# ospi_v143.net
KiCad netlist of a schematic drawn in EAGLE
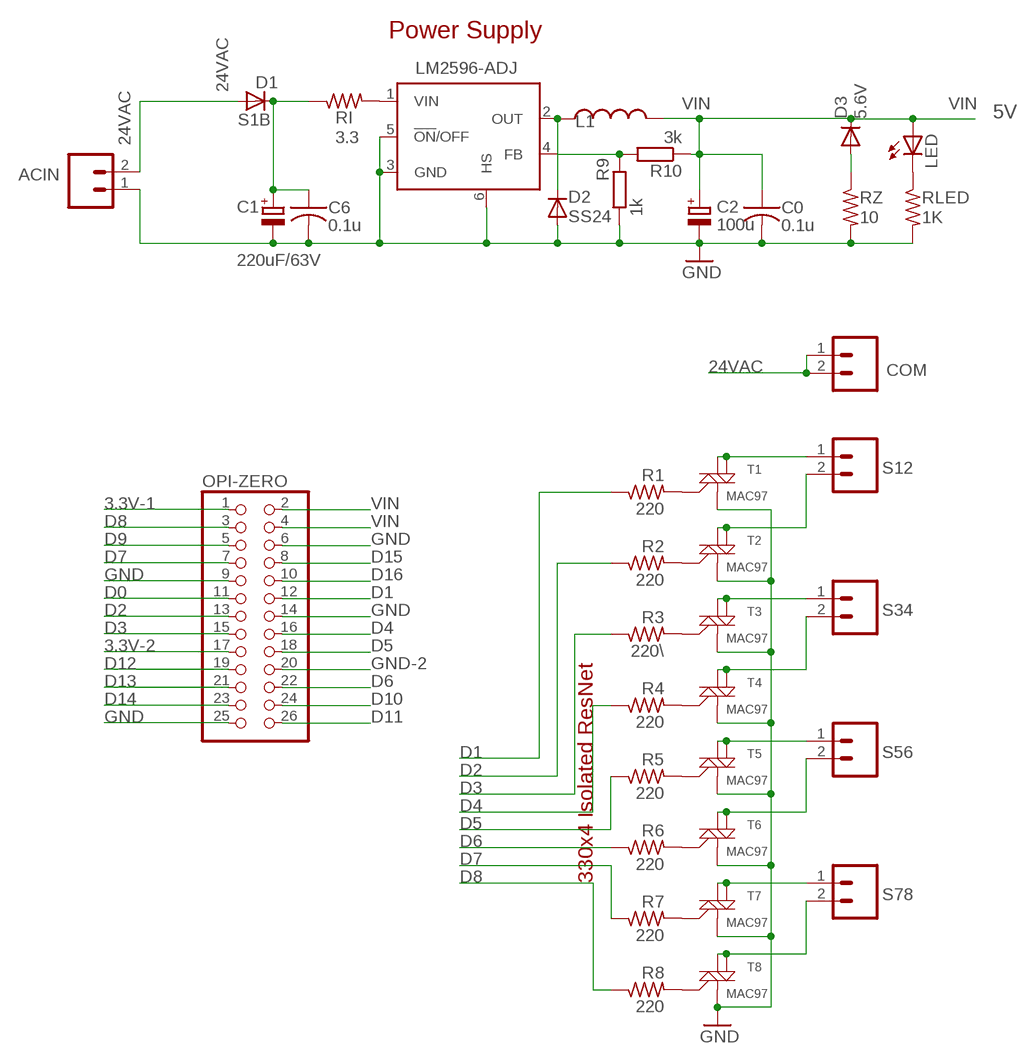
[diagram p0: schematic, sheet 1]

(export (version "E")
  (design (tool "Eeschema 10.0.6"))
  (components
    (comp (ref "ACIN")
      (value "M025MM-X")
      (footprint "eagle-import:SCREWTERMINAL-5MM-2-X")
      (libsource (lib "eagle-import") (part "M025MM-X"))
    )
    (comp (ref "C0")
      (value "0.1u")
      (footprint "eagle-import:C1206")
      (libsource (lib "eagle-import") (part "C-USC1206"))
    )
    (comp (ref "C1")
      (value "220uF/63V")
      (footprint "eagle-import:PANASONIC_E")
      (libsource (lib "eagle-import") (part "CPOL-EUE"))
    )
    (comp (ref "C2")
      (value "100u")
      (footprint "eagle-import:PANASONIC_E")
      (libsource (lib "eagle-import") (part "CPOL-EUE"))
    )
    (comp (ref "C6")
      (value "0.1u")
      (footprint "eagle-import:C1206")
      (libsource (lib "eagle-import") (part "C-USC1206"))
    )
    (comp (ref "COM")
      (value "M025MM-X")
      (footprint "eagle-import:SCREWTERMINAL-5MM-2-X")
      (libsource (lib "eagle-import") (part "M025MM-X"))
    )
    (comp (ref "D1")
      (value "S1B")
      (footprint "eagle-import:DO-214AC")
      (libsource (lib "eagle-import") (part "DIODE-DO-214AC"))
    )
    (comp (ref "D2")
      (value "SS24")
      (footprint "eagle-import:SMB")
      (libsource (lib "eagle-import") (part "DIODE-SMB"))
    )
    (comp (ref "D3")
      (value "5.6V")
      (footprint "eagle-import:MINIMELF")
      (libsource (lib "eagle-import") (part "DIODE-MINIMELF"))
    )
    (comp (ref "L1")
      (value "150uH")
      (footprint "eagle-import:CDRH125")
      (libsource (lib "eagle-import") (part "INDUCTORPWR"))
    )
    (comp (ref "LED")
      (value "LEDCHIPLED_0805")
      (footprint "eagle-import:CHIPLED_0805")
      (libsource (lib "eagle-import") (part "LEDCHIPLED_0805"))
    )
    (comp (ref "LM2596-ADJ")
      (value "LM2596-ADJ")
      (footprint "eagle-import:TO263-5")
      (fields (field (name "MF") "NATIONAL SEMICONDUCTOR") (field (name "MPN") "LM2596S-ADJ/NOPB"))
      (libsource (lib "eagle-import") (part "LM2596S"))
    )
    (comp (ref "OPI-ZERO")
      (value "PINHD-2X13")
      (footprint "eagle-import:2X13")
      (libsource (lib "eagle-import") (part "PINHD-2X13"))
    )
    (comp (ref "R1")
      (value "220")
      (footprint "eagle-import:R0603")
      (libsource (lib "eagle-import") (part "R-US_R0603"))
    )
    (comp (ref "R2")
      (value "220")
      (footprint "eagle-import:R0603")
      (libsource (lib "eagle-import") (part "R-US_R0603"))
    )
    (comp (ref "R3")
      (value "220\\")
      (footprint "eagle-import:R0603")
      (libsource (lib "eagle-import") (part "R-US_R0603"))
    )
    (comp (ref "R4")
      (value "220")
      (footprint "eagle-import:R0603")
      (libsource (lib "eagle-import") (part "R-US_R0603"))
    )
    (comp (ref "R5")
      (value "220")
      (footprint "eagle-import:R0603")
      (libsource (lib "eagle-import") (part "R-US_R0603"))
    )
    (comp (ref "R6")
      (value "220")
      (footprint "eagle-import:R0603")
      (libsource (lib "eagle-import") (part "R-US_R0603"))
    )
    (comp (ref "R7")
      (value "220")
      (footprint "eagle-import:R0603")
      (libsource (lib "eagle-import") (part "R-US_R0603"))
    )
    (comp (ref "R8")
      (value "220")
      (footprint "eagle-import:R0603")
      (libsource (lib "eagle-import") (part "R-US_R0603"))
    )
    (comp (ref "R9")
      (value "1k")
      (footprint "eagle-import:M0805")
      (libsource (lib "eagle-import") (part "R-EU_M0805"))
    )
    (comp (ref "R10")
      (value "3k")
      (footprint "eagle-import:M0805")
      (libsource (lib "eagle-import") (part "R-EU_M0805"))
    )
    (comp (ref "RI")
      (value "3.3")
      (footprint "eagle-import:R2010")
      (libsource (lib "eagle-import") (part "adafruitGood_R-US_R2010"))
    )
    (comp (ref "RLED")
      (value "1K")
      (footprint "eagle-import:R1206")
      (libsource (lib "eagle-import") (part "R-US_R1206"))
    )
    (comp (ref "RZ")
      (value "10")
      (footprint "eagle-import:R2010")
      (libsource (lib "eagle-import") (part "R-US_R2010"))
    )
    (comp (ref "S12")
      (value "M025MM-X")
      (footprint "eagle-import:SCREWTERMINAL-5MM-2-X")
      (libsource (lib "eagle-import") (part "M025MM-X"))
    )
    (comp (ref "S34")
      (value "M025MM-X")
      (footprint "eagle-import:SCREWTERMINAL-5MM-2-X")
      (libsource (lib "eagle-import") (part "M025MM-X"))
    )
    (comp (ref "S56")
      (value "M025MM-X")
      (footprint "eagle-import:SCREWTERMINAL-5MM-2-X")
      (libsource (lib "eagle-import") (part "M025MM-X"))
    )
    (comp (ref "S78")
      (value "M025MM-X")
      (footprint "eagle-import:SCREWTERMINAL-5MM-2-X")
      (libsource (lib "eagle-import") (part "M025MM-X"))
    )
    (comp (ref "T1")
      (value "MAC97")
      (footprint "eagle-import:SOT223")
      (libsource (lib "eagle-import") (part "MAC97SOT223"))
    )
    (comp (ref "T2")
      (value "MAC97")
      (footprint "eagle-import:SOT223")
      (libsource (lib "eagle-import") (part "MAC97SOT223"))
    )
    (comp (ref "T3")
      (value "MAC97")
      (footprint "eagle-import:SOT223")
      (libsource (lib "eagle-import") (part "MAC97SOT223"))
    )
    (comp (ref "T4")
      (value "MAC97")
      (footprint "eagle-import:SOT223")
      (libsource (lib "eagle-import") (part "MAC97SOT223"))
    )
    (comp (ref "T5")
      (value "MAC97")
      (footprint "eagle-import:SOT223")
      (libsource (lib "eagle-import") (part "MAC97SOT223"))
    )
    (comp (ref "T6")
      (value "MAC97")
      (footprint "eagle-import:SOT223")
      (libsource (lib "eagle-import") (part "MAC97SOT223"))
    )
    (comp (ref "T7")
      (value "MAC97")
      (footprint "eagle-import:SOT223")
      (libsource (lib "eagle-import") (part "MAC97SOT223"))
    )
    (comp (ref "T8")
      (value "MAC97")
      (footprint "eagle-import:SOT223")
      (libsource (lib "eagle-import") (part "MAC97SOT223"))
    )
  )
  (nets
    (net (code "1") (name "/3.3V-1") (class "Default")
      (node (ref "OPI-ZERO") (pin "1") (pinfunction "1_1") (pintype "passive"))
    )
    (net (code "2") (name "/3.3V-2") (class "Default")
      (node (ref "OPI-ZERO") (pin "17") (pinfunction "17_17") (pintype "passive"))
    )
    (net (code "3") (name "/24VAC") (class "Default")
      (node (ref "ACIN") (pin "2") (pinfunction "2_2") (pintype "passive"))
      (node (ref "COM") (pin "1") (pinfunction "1_1") (pintype "passive"))
      (node (ref "COM") (pin "2") (pinfunction "2_2") (pintype "passive"))
      (node (ref "D1") (pin "A") (pinfunction "A_A") (pintype "passive"))
    )
    (net (code "4") (name "/D0") (class "Default")
      (node (ref "OPI-ZERO") (pin "11") (pinfunction "11_11") (pintype "passive"))
    )
    (net (code "5") (name "/D1") (class "Default")
      (node (ref "OPI-ZERO") (pin "12") (pinfunction "12_12") (pintype "passive"))
      (node (ref "R1") (pin "1") (pinfunction "1_1") (pintype "passive"))
    )
    (net (code "6") (name "/D2") (class "Default")
      (node (ref "OPI-ZERO") (pin "13") (pinfunction "13_13") (pintype "passive"))
      (node (ref "R2") (pin "1") (pinfunction "1_1") (pintype "passive"))
    )
    (net (code "7") (name "/D3") (class "Default")
      (node (ref "OPI-ZERO") (pin "15") (pinfunction "15_15") (pintype "passive"))
      (node (ref "R3") (pin "1") (pinfunction "1_1") (pintype "passive"))
    )
    (net (code "8") (name "/D4") (class "Default")
      (node (ref "OPI-ZERO") (pin "16") (pinfunction "16_16") (pintype "passive"))
      (node (ref "R4") (pin "1") (pinfunction "1_1") (pintype "passive"))
    )
    (net (code "9") (name "/D5") (class "Default")
      (node (ref "OPI-ZERO") (pin "18") (pinfunction "18_18") (pintype "passive"))
      (node (ref "R5") (pin "1") (pinfunction "1_1") (pintype "passive"))
    )
    (net (code "10") (name "/D6") (class "Default")
      (node (ref "OPI-ZERO") (pin "22") (pinfunction "22_22") (pintype "passive"))
      (node (ref "R6") (pin "1") (pinfunction "1_1") (pintype "passive"))
    )
    (net (code "11") (name "/D7") (class "Default")
      (node (ref "OPI-ZERO") (pin "7") (pinfunction "7_7") (pintype "passive"))
      (node (ref "R7") (pin "1") (pinfunction "1_1") (pintype "passive"))
    )
    (net (code "12") (name "/D8") (class "Default")
      (node (ref "OPI-ZERO") (pin "3") (pinfunction "3_3") (pintype "passive"))
      (node (ref "R8") (pin "1") (pinfunction "1_1") (pintype "passive"))
    )
    (net (code "13") (name "/D9") (class "Default")
      (node (ref "OPI-ZERO") (pin "5") (pinfunction "5_5") (pintype "passive"))
    )
    (net (code "14") (name "/D10") (class "Default")
      (node (ref "OPI-ZERO") (pin "24") (pinfunction "24_24") (pintype "passive"))
    )
    (net (code "15") (name "/D11") (class "Default")
      (node (ref "OPI-ZERO") (pin "26") (pinfunction "26_26") (pintype "passive"))
    )
    (net (code "16") (name "/D12") (class "Default")
      (node (ref "OPI-ZERO") (pin "19") (pinfunction "19_19") (pintype "passive"))
    )
    (net (code "17") (name "/D13") (class "Default")
      (node (ref "OPI-ZERO") (pin "21") (pinfunction "21_21") (pintype "passive"))
    )
    (net (code "18") (name "/D14") (class "Default")
      (node (ref "OPI-ZERO") (pin "23") (pinfunction "23_23") (pintype "passive"))
    )
    (net (code "19") (name "/D15") (class "Default")
      (node (ref "OPI-ZERO") (pin "8") (pinfunction "8_8") (pintype "passive"))
    )
    (net (code "20") (name "/D16") (class "Default")
      (node (ref "OPI-ZERO") (pin "10") (pinfunction "10_10") (pintype "passive"))
    )
    (net (code "21") (name "/GND-2") (class "Default")
      (node (ref "OPI-ZERO") (pin "20") (pinfunction "20_20") (pintype "passive"))
    )
    (net (code "22") (name "/VIN") (class "Default")
      (node (ref "C0") (pin "1") (pinfunction "1_1") (pintype "passive"))
      (node (ref "C2") (pin "+") (pinfunction "+_+") (pintype "passive"))
      (node (ref "D3") (pin "C") (pinfunction "C_C") (pintype "passive"))
      (node (ref "L1") (pin "2") (pinfunction "2_2") (pintype "passive"))
      (node (ref "LED") (pin "A") (pinfunction "A_A") (pintype "passive"))
      (node (ref "OPI-ZERO") (pin "2") (pinfunction "2_2") (pintype "passive"))
      (node (ref "OPI-ZERO") (pin "4") (pinfunction "4_4") (pintype "passive"))
      (node (ref "R10") (pin "1") (pinfunction "1_1") (pintype "passive"))
    )
    (net (code "23") (name "GND") (class "Default")
      (node (ref "ACIN") (pin "1") (pinfunction "1_1") (pintype "passive"))
      (node (ref "C0") (pin "2") (pinfunction "2_2") (pintype "passive"))
      (node (ref "C1") (pin "-") (pinfunction "-_-") (pintype "passive"))
      (node (ref "C2") (pin "-") (pinfunction "-_-") (pintype "passive"))
      (node (ref "C6") (pin "2") (pinfunction "2_2") (pintype "passive"))
      (node (ref "D2") (pin "A") (pinfunction "A_A") (pintype "passive"))
      (node (ref "LM2596-ADJ") (pin "3") (pinfunction "GND_3") (pintype "power_in"))
      (node (ref "LM2596-ADJ") (pin "5") (pinfunction "~{ON}/OFF_5") (pintype "input"))
      (node (ref "LM2596-ADJ") (pin "6") (pinfunction "HS_6") (pintype "power_in"))
      (node (ref "OPI-ZERO") (pin "14") (pinfunction "14_14") (pintype "passive"))
      (node (ref "OPI-ZERO") (pin "25") (pinfunction "25_25") (pintype "passive"))
      (node (ref "OPI-ZERO") (pin "6") (pinfunction "6_6") (pintype "passive"))
      (node (ref "OPI-ZERO") (pin "9") (pinfunction "9_9") (pintype "passive"))
      (node (ref "R9") (pin "1") (pinfunction "1_1") (pintype "passive"))
      (node (ref "RLED") (pin "2") (pinfunction "2_2") (pintype "passive"))
      (node (ref "RZ") (pin "2") (pinfunction "2_2") (pintype "passive"))
      (node (ref "T1") (pin "1") (pinfunction "M1_1") (pintype "bidirectional"))
      (node (ref "T2") (pin "1") (pinfunction "M1_1") (pintype "bidirectional"))
      (node (ref "T3") (pin "1") (pinfunction "M1_1") (pintype "bidirectional"))
      (node (ref "T4") (pin "1") (pinfunction "M1_1") (pintype "bidirectional"))
      (node (ref "T5") (pin "1") (pinfunction "M1_1") (pintype "bidirectional"))
      (node (ref "T6") (pin "1") (pinfunction "M1_1") (pintype "bidirectional"))
      (node (ref "T7") (pin "1") (pinfunction "M1_1") (pintype "bidirectional"))
      (node (ref "T8") (pin "1") (pinfunction "M1_1") (pintype "bidirectional"))
    )
    (net (code "24") (name "Net-(C1-Pad+)") (class "Default")
      (node (ref "C1") (pin "+") (pinfunction "+_+") (pintype "passive"))
      (node (ref "C6") (pin "1") (pinfunction "1_1") (pintype "passive"))
      (node (ref "D1") (pin "C") (pinfunction "C_C") (pintype "passive"))
      (node (ref "RI") (pin "1") (pinfunction "1_1") (pintype "passive"))
    )
    (net (code "25") (name "Net-(D3-PadA)") (class "Default")
      (node (ref "D3") (pin "A") (pinfunction "A_A") (pintype "passive"))
      (node (ref "RZ") (pin "1") (pinfunction "1_1") (pintype "passive"))
    )
    (net (code "26") (name "Net-(LED-PadC)") (class "Default")
      (node (ref "LED") (pin "C") (pinfunction "C_C") (pintype "passive"))
      (node (ref "RLED") (pin "1") (pinfunction "1_1") (pintype "passive"))
    )
    (net (code "27") (name "Net-(LM2596-ADJ-FB)") (class "Default")
      (node (ref "LM2596-ADJ") (pin "4") (pinfunction "FB_4") (pintype "input"))
      (node (ref "R10") (pin "2") (pinfunction "2_2") (pintype "passive"))
      (node (ref "R9") (pin "2") (pinfunction "2_2") (pintype "passive"))
    )
    (net (code "28") (name "Net-(LM2596-ADJ-OUT)") (class "Default")
      (node (ref "D2") (pin "C") (pinfunction "C_C") (pintype "passive"))
      (node (ref "L1") (pin "1") (pinfunction "1_1") (pintype "passive"))
      (node (ref "LM2596-ADJ") (pin "2") (pinfunction "OUT_2") (pintype "output"))
    )
    (net (code "29") (name "Net-(LM2596-ADJ-VIN)") (class "Default")
      (node (ref "LM2596-ADJ") (pin "1") (pinfunction "VIN_1") (pintype "input"))
      (node (ref "RI") (pin "2") (pinfunction "2_2") (pintype "passive"))
    )
    (net (code "30") (name "Net-(T1-G)") (class "Default")
      (node (ref "R1") (pin "2") (pinfunction "2_2") (pintype "passive"))
      (node (ref "T1") (pin "3") (pinfunction "G_3") (pintype "bidirectional"))
    )
    (net (code "31") (name "Net-(T1-M2)") (class "Default")
      (node (ref "S12") (pin "1") (pinfunction "1_1") (pintype "passive"))
      (node (ref "T1") (pin "2") (pinfunction "M2_2") (pintype "bidirectional"))
      (node (ref "T1") (pin "4") (pinfunction "M2-4_4") (pintype "bidirectional"))
    )
    (net (code "32") (name "Net-(T2-G)") (class "Default")
      (node (ref "R2") (pin "2") (pinfunction "2_2") (pintype "passive"))
      (node (ref "T2") (pin "3") (pinfunction "G_3") (pintype "bidirectional"))
    )
    (net (code "33") (name "Net-(T2-M2)") (class "Default")
      (node (ref "S12") (pin "2") (pinfunction "2_2") (pintype "passive"))
      (node (ref "T2") (pin "2") (pinfunction "M2_2") (pintype "bidirectional"))
      (node (ref "T2") (pin "4") (pinfunction "M2-4_4") (pintype "bidirectional"))
    )
    (net (code "34") (name "Net-(T3-G)") (class "Default")
      (node (ref "R3") (pin "2") (pinfunction "2_2") (pintype "passive"))
      (node (ref "T3") (pin "3") (pinfunction "G_3") (pintype "bidirectional"))
    )
    (net (code "35") (name "Net-(T3-M2)") (class "Default")
      (node (ref "S34") (pin "1") (pinfunction "1_1") (pintype "passive"))
      (node (ref "T3") (pin "2") (pinfunction "M2_2") (pintype "bidirectional"))
      (node (ref "T3") (pin "4") (pinfunction "M2-4_4") (pintype "bidirectional"))
    )
    (net (code "36") (name "Net-(T4-G)") (class "Default")
      (node (ref "R4") (pin "2") (pinfunction "2_2") (pintype "passive"))
      (node (ref "T4") (pin "3") (pinfunction "G_3") (pintype "bidirectional"))
    )
    (net (code "37") (name "Net-(T4-M2)") (class "Default")
      (node (ref "S34") (pin "2") (pinfunction "2_2") (pintype "passive"))
      (node (ref "T4") (pin "2") (pinfunction "M2_2") (pintype "bidirectional"))
      (node (ref "T4") (pin "4") (pinfunction "M2-4_4") (pintype "bidirectional"))
    )
    (net (code "38") (name "Net-(T5-G)") (class "Default")
      (node (ref "R5") (pin "2") (pinfunction "2_2") (pintype "passive"))
      (node (ref "T5") (pin "3") (pinfunction "G_3") (pintype "bidirectional"))
    )
    (net (code "39") (name "Net-(T5-M2)") (class "Default")
      (node (ref "S56") (pin "1") (pinfunction "1_1") (pintype "passive"))
      (node (ref "T5") (pin "2") (pinfunction "M2_2") (pintype "bidirectional"))
      (node (ref "T5") (pin "4") (pinfunction "M2-4_4") (pintype "bidirectional"))
    )
    (net (code "40") (name "Net-(T6-G)") (class "Default")
      (node (ref "R6") (pin "2") (pinfunction "2_2") (pintype "passive"))
      (node (ref "T6") (pin "3") (pinfunction "G_3") (pintype "bidirectional"))
    )
    (net (code "41") (name "Net-(T6-M2)") (class "Default")
      (node (ref "S56") (pin "2") (pinfunction "2_2") (pintype "passive"))
      (node (ref "T6") (pin "2") (pinfunction "M2_2") (pintype "bidirectional"))
      (node (ref "T6") (pin "4") (pinfunction "M2-4_4") (pintype "bidirectional"))
    )
    (net (code "42") (name "Net-(T7-G)") (class "Default")
      (node (ref "R7") (pin "2") (pinfunction "2_2") (pintype "passive"))
      (node (ref "T7") (pin "3") (pinfunction "G_3") (pintype "bidirectional"))
    )
    (net (code "43") (name "Net-(T7-M2)") (class "Default")
      (node (ref "S78") (pin "1") (pinfunction "1_1") (pintype "passive"))
      (node (ref "T7") (pin "2") (pinfunction "M2_2") (pintype "bidirectional"))
      (node (ref "T7") (pin "4") (pinfunction "M2-4_4") (pintype "bidirectional"))
    )
    (net (code "44") (name "Net-(T8-G)") (class "Default")
      (node (ref "R8") (pin "2") (pinfunction "2_2") (pintype "passive"))
      (node (ref "T8") (pin "3") (pinfunction "G_3") (pintype "bidirectional"))
    )
    (net (code "45") (name "Net-(T8-M2)") (class "Default")
      (node (ref "S78") (pin "2") (pinfunction "2_2") (pintype "passive"))
      (node (ref "T8") (pin "2") (pinfunction "M2_2") (pintype "bidirectional"))
      (node (ref "T8") (pin "4") (pinfunction "M2-4_4") (pintype "bidirectional"))
    )
  )
)
